# sideways.net
KiCad netlist of a schematic drawn in EAGLE
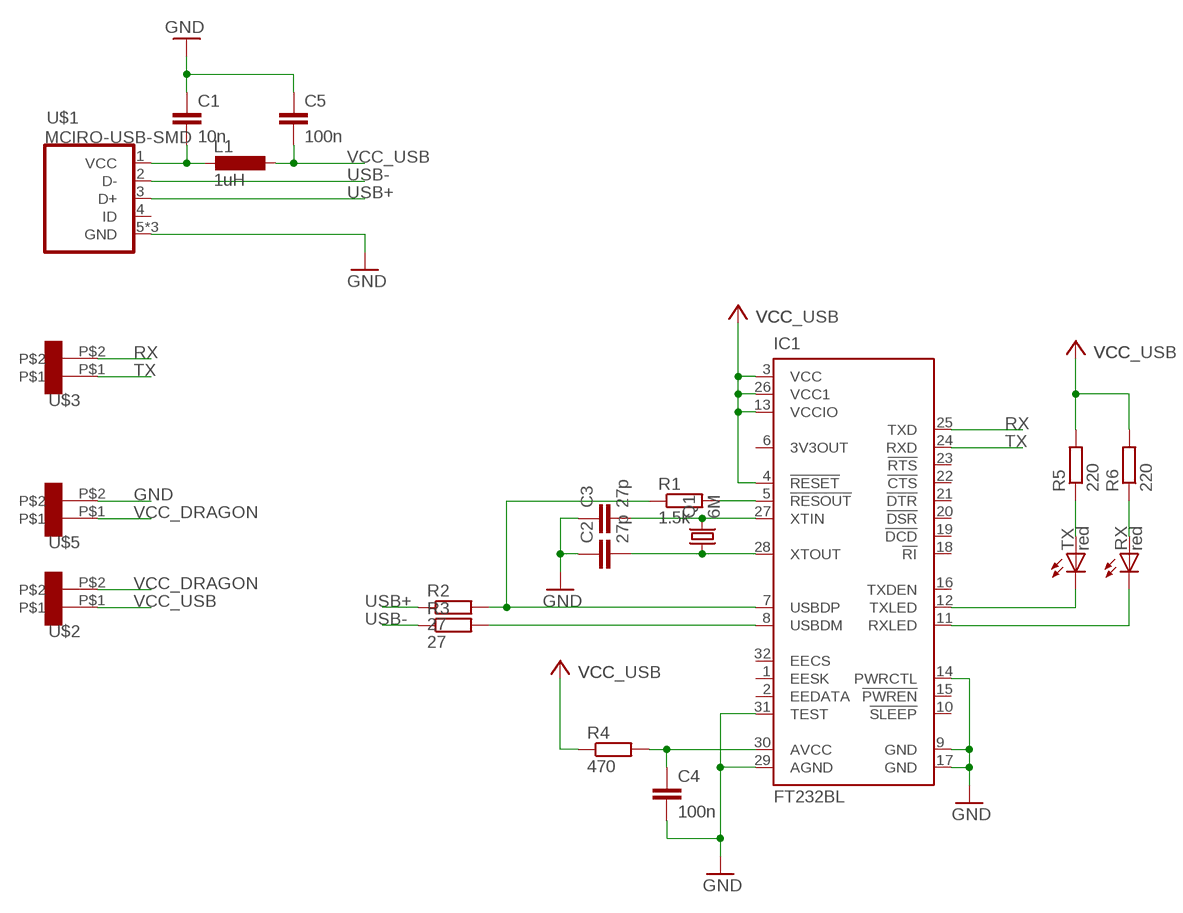
[diagram p0: schematic, sheet 1]

(export (version "E")
  (design (tool "Eeschema 10.0.6"))
  (components
    (comp (ref "C1")
      (value "10n")
      (footprint "eagle-import:C0603")
      (libsource (lib "eagle-import") (part "C-EUC0603"))
    )
    (comp (ref "C2")
      (value "27p")
      (footprint "eagle-import:C0603")
      (libsource (lib "eagle-import") (part "C-EUC0603"))
    )
    (comp (ref "C3")
      (value "27p")
      (footprint "eagle-import:C0603")
      (libsource (lib "eagle-import") (part "C-EUC0603"))
    )
    (comp (ref "C4")
      (value "100n")
      (footprint "eagle-import:C0603")
      (libsource (lib "eagle-import") (part "C-EUC0603"))
    )
    (comp (ref "C5")
      (value "100n")
      (footprint "eagle-import:C0603")
      (libsource (lib "eagle-import") (part "C-EUC0603"))
    )
    (comp (ref "IC1")
      (value "FT232BL")
      (footprint "eagle-import:LQFP32-7X7")
      (fields (field (name "MF") "FARNELL") (field (name "MPN") "FT232BL/TR"))
      (libsource (lib "eagle-import") (part "FT232BL"))
    )
    (comp (ref "L1")
      (value "1uH")
      (footprint "eagle-import:L0603")
      (libsource (lib "eagle-import") (part "L-EUL0603"))
    )
    (comp (ref "Q1")
      (value "6M")
      (footprint "eagle-import:HC49U-V")
      (libsource (lib "eagle-import") (part "CRYSTALHC49U-V"))
    )
    (comp (ref "R1")
      (value "1.5k")
      (footprint "eagle-import:R0603")
      (libsource (lib "eagle-import") (part "R-EU_R0603"))
    )
    (comp (ref "R2")
      (value "27")
      (footprint "eagle-import:R0603")
      (libsource (lib "eagle-import") (part "R-EU_R0603"))
    )
    (comp (ref "R3")
      (value "27")
      (footprint "eagle-import:R0603")
      (libsource (lib "eagle-import") (part "R-EU_R0603"))
    )
    (comp (ref "R4")
      (value "470")
      (footprint "eagle-import:R0603")
      (libsource (lib "eagle-import") (part "R-EU_R0603"))
    )
    (comp (ref "R5")
      (value "220")
      (footprint "eagle-import:R0603")
      (libsource (lib "eagle-import") (part "R-EU_R0603"))
    )
    (comp (ref "R6")
      (value "220")
      (footprint "eagle-import:R0603")
      (libsource (lib "eagle-import") (part "R-EU_R0603"))
    )
    (comp (ref "RX")
      (value "red")
      (footprint "eagle-import:C0603")
      (libsource (lib "eagle-import") (part "LED_0603"))
    )
    (comp (ref "TX")
      (value "red")
      (footprint "eagle-import:C0603")
      (libsource (lib "eagle-import") (part "LED_0603"))
    )
    (comp (ref "U$1")
      (value "MCIRO-USB-SMD")
      (footprint "eagle-import:MICRO-USB-3")
      (libsource (lib "eagle-import") (part "MCIRO-USB-SMD"))
    )
    (comp (ref "U$2")
      (value "CON_DIL_2")
      (footprint "eagle-import:CON_DIL_2")
      (libsource (lib "eagle-import") (part "CON_DIL_2"))
    )
    (comp (ref "U$3")
      (value "CON_DIL_2")
      (footprint "eagle-import:CON_DIL_2")
      (libsource (lib "eagle-import") (part "CON_DIL_2"))
    )
    (comp (ref "U$5")
      (value "CON_DIL_2")
      (footprint "eagle-import:CON_DIL_2")
      (libsource (lib "eagle-import") (part "CON_DIL_2"))
    )
  )
  (nets
    (net (code "1") (name "/RX") (class "Default")
      (node (ref "IC1") (pin "25") (pinfunction "TXD_25") (pintype "output"))
      (node (ref "U$3") (pin "P$2") (pinfunction "P$2_P$2") (pintype "bidirectional"))
    )
    (net (code "2") (name "/TX") (class "Default")
      (node (ref "IC1") (pin "24") (pinfunction "RXD_24") (pintype "input"))
      (node (ref "U$3") (pin "P$1") (pinfunction "P$1_P$1") (pintype "bidirectional"))
    )
    (net (code "3") (name "/USB+") (class "Default")
      (node (ref "R2") (pin "1") (pinfunction "1_1") (pintype "passive"))
      (node (ref "U$1") (pin "3") (pinfunction "D+_3") (pintype "bidirectional"))
    )
    (net (code "4") (name "/USB-") (class "Default")
      (node (ref "R3") (pin "1") (pinfunction "1_1") (pintype "passive"))
      (node (ref "U$1") (pin "2") (pinfunction "D-_2") (pintype "bidirectional"))
    )
    (net (code "5") (name "/VCC_DRAGON") (class "Default")
      (node (ref "U$2") (pin "P$2") (pinfunction "P$2_P$2") (pintype "bidirectional"))
      (node (ref "U$5") (pin "P$1") (pinfunction "P$1_P$1") (pintype "bidirectional"))
    )
    (net (code "6") (name "GND") (class "Default")
      (node (ref "C1") (pin "1") (pinfunction "1_1") (pintype "passive"))
      (node (ref "C2") (pin "1") (pinfunction "1_1") (pintype "passive"))
      (node (ref "C3") (pin "1") (pinfunction "1_1") (pintype "passive"))
      (node (ref "C4") (pin "2") (pinfunction "2_2") (pintype "passive"))
      (node (ref "C5") (pin "1") (pinfunction "1_1") (pintype "passive"))
      (node (ref "IC1") (pin "14") (pinfunction "PWRCTL_14") (pintype "bidirectional"))
      (node (ref "IC1") (pin "17") (pinfunction "GND_17") (pintype "power_in"))
      (node (ref "IC1") (pin "29") (pinfunction "AGND_29") (pintype "power_in"))
      (node (ref "IC1") (pin "31") (pinfunction "TEST_31") (pintype "input"))
      (node (ref "IC1") (pin "9") (pinfunction "GND_9") (pintype "power_in"))
      (node (ref "U$1") (pin "5") (pinfunction "GND_5") (pintype "power_in"))
      (node (ref "U$1") (pin "GND0") (pinfunction "GND_GND0") (pintype "power_in"))
      (node (ref "U$1") (pin "GND1") (pinfunction "GND_GND1") (pintype "power_in"))
      (node (ref "U$5") (pin "P$2") (pinfunction "P$2_P$2") (pintype "bidirectional"))
    )
    (net (code "7") (name "Net-(IC1-AVCC)") (class "Default")
      (node (ref "C4") (pin "1") (pinfunction "1_1") (pintype "passive"))
      (node (ref "IC1") (pin "30") (pinfunction "AVCC_30") (pintype "power_in"))
      (node (ref "R4") (pin "2") (pinfunction "2_2") (pintype "passive"))
    )
    (net (code "8") (name "Net-(IC1-RXLED)") (class "Default")
      (node (ref "IC1") (pin "11") (pinfunction "RXLED_11") (pintype "bidirectional"))
      (node (ref "RX") (pin "N") (pinfunction "N_N") (pintype "passive"))
    )
    (net (code "9") (name "Net-(IC1-TXLED)") (class "Default")
      (node (ref "IC1") (pin "12") (pinfunction "TXLED_12") (pintype "bidirectional"))
      (node (ref "TX") (pin "N") (pinfunction "N_N") (pintype "passive"))
    )
    (net (code "10") (name "Net-(IC1-USBDM)") (class "Default")
      (node (ref "IC1") (pin "8") (pinfunction "USBDM_8") (pintype "bidirectional"))
      (node (ref "R3") (pin "2") (pinfunction "2_2") (pintype "passive"))
    )
    (net (code "11") (name "Net-(IC1-USBDP)") (class "Default")
      (node (ref "IC1") (pin "7") (pinfunction "USBDP_7") (pintype "bidirectional"))
      (node (ref "R1") (pin "1") (pinfunction "1_1") (pintype "passive"))
      (node (ref "R2") (pin "2") (pinfunction "2_2") (pintype "passive"))
    )
    (net (code "12") (name "Net-(IC1-XTIN)") (class "Default")
      (node (ref "C3") (pin "2") (pinfunction "2_2") (pintype "passive"))
      (node (ref "IC1") (pin "27") (pinfunction "XTIN_27") (pintype "input"))
      (node (ref "Q1") (pin "2") (pinfunction "2_2") (pintype "passive"))
    )
    (net (code "13") (name "Net-(IC1-XTOUT)") (class "Default")
      (node (ref "C2") (pin "2") (pinfunction "2_2") (pintype "passive"))
      (node (ref "IC1") (pin "28") (pinfunction "XTOUT_28") (pintype "output"))
      (node (ref "Q1") (pin "1") (pinfunction "1_1") (pintype "passive"))
    )
    (net (code "14") (name "Net-(IC1-~{RESOUT})") (class "Default")
      (node (ref "IC1") (pin "5") (pinfunction "~{RESOUT}_5") (pintype "input"))
      (node (ref "R1") (pin "2") (pinfunction "2_2") (pintype "passive"))
    )
    (net (code "15") (name "Net-(R5-Pad1)") (class "Default")
      (node (ref "R5") (pin "1") (pinfunction "1_1") (pintype "passive"))
      (node (ref "TX") (pin "P") (pinfunction "P_P") (pintype "passive"))
    )
    (net (code "16") (name "Net-(R6-Pad1)") (class "Default")
      (node (ref "R6") (pin "1") (pinfunction "1_1") (pintype "passive"))
      (node (ref "RX") (pin "P") (pinfunction "P_P") (pintype "passive"))
    )
    (net (code "17") (name "Net-(U$1-VCC)") (class "Default")
      (node (ref "C1") (pin "2") (pinfunction "2_2") (pintype "passive"))
      (node (ref "L1") (pin "2") (pinfunction "2_2") (pintype "passive"))
      (node (ref "U$1") (pin "1") (pinfunction "VCC_1") (pintype "power_in"))
    )
    (net (code "18") (name "VCC") (class "Default")
      (node (ref "C5") (pin "2") (pinfunction "2_2") (pintype "passive"))
      (node (ref "IC1") (pin "13") (pinfunction "VCCIO_13") (pintype "power_in"))
      (node (ref "IC1") (pin "26") (pinfunction "VCC1_26") (pintype "power_in"))
      (node (ref "IC1") (pin "3") (pinfunction "VCC_3") (pintype "power_in"))
      (node (ref "IC1") (pin "4") (pinfunction "~{RESET}_4") (pintype "input"))
      (node (ref "L1") (pin "1") (pinfunction "1_1") (pintype "passive"))
      (node (ref "R4") (pin "1") (pinfunction "1_1") (pintype "passive"))
      (node (ref "R5") (pin "2") (pinfunction "2_2") (pintype "passive"))
      (node (ref "R6") (pin "2") (pinfunction "2_2") (pintype "passive"))
      (node (ref "U$2") (pin "P$1") (pinfunction "P$1_P$1") (pintype "bidirectional"))
    )
    (net (code "19") (name "unconnected-(IC1-3V3OUT-Pad6)") (class "Default")
      (node (ref "IC1") (pin "6") (pinfunction "3V3OUT_6") (pintype "output"))
    )
    (net (code "20") (name "unconnected-(IC1-EECS-Pad32)") (class "Default")
      (node (ref "IC1") (pin "32") (pinfunction "EECS_32") (pintype "input"))
    )
    (net (code "21") (name "unconnected-(IC1-EEDATA-Pad2)") (class "Default")
      (node (ref "IC1") (pin "2") (pinfunction "EEDATA_2") (pintype "input"))
    )
    (net (code "22") (name "unconnected-(IC1-EESK-Pad1)") (class "Default")
      (node (ref "IC1") (pin "1") (pinfunction "EESK_1") (pintype "input"))
    )
    (net (code "23") (name "unconnected-(IC1-TXDEN-Pad16)") (class "Default")
      (node (ref "IC1") (pin "16") (pinfunction "TXDEN_16") (pintype "bidirectional"))
    )
    (net (code "24") (name "unconnected-(IC1-~{CTS}-Pad22)") (class "Default")
      (node (ref "IC1") (pin "22") (pinfunction "~{CTS}_22") (pintype "input"))
    )
    (net (code "25") (name "unconnected-(IC1-~{DCD}-Pad19)") (class "Default")
      (node (ref "IC1") (pin "19") (pinfunction "~{DCD}_19") (pintype "input"))
    )
    (net (code "26") (name "unconnected-(IC1-~{DSR}-Pad20)") (class "Default")
      (node (ref "IC1") (pin "20") (pinfunction "~{DSR}_20") (pintype "input"))
    )
    (net (code "27") (name "unconnected-(IC1-~{DTR}-Pad21)") (class "Default")
      (node (ref "IC1") (pin "21") (pinfunction "~{DTR}_21") (pintype "output"))
    )
    (net (code "28") (name "unconnected-(IC1-~{PWREN}-Pad15)") (class "Default")
      (node (ref "IC1") (pin "15") (pinfunction "~{PWREN}_15") (pintype "bidirectional"))
    )
    (net (code "29") (name "unconnected-(IC1-~{RI}-Pad18)") (class "Default")
      (node (ref "IC1") (pin "18") (pinfunction "~{RI}_18") (pintype "input"))
    )
    (net (code "30") (name "unconnected-(IC1-~{RTS}-Pad23)") (class "Default")
      (node (ref "IC1") (pin "23") (pinfunction "~{RTS}_23") (pintype "output"))
    )
    (net (code "31") (name "unconnected-(IC1-~{SLEEP}-Pad10)") (class "Default")
      (node (ref "IC1") (pin "10") (pinfunction "~{SLEEP}_10") (pintype "input"))
    )
    (net (code "32") (name "unconnected-(U$1-ID-Pad4)") (class "Default")
      (node (ref "U$1") (pin "4") (pinfunction "ID_4") (pintype "bidirectional"))
    )
  )
)
